# Main.net
KiCad netlist of a schematic drawn in Altium Designer
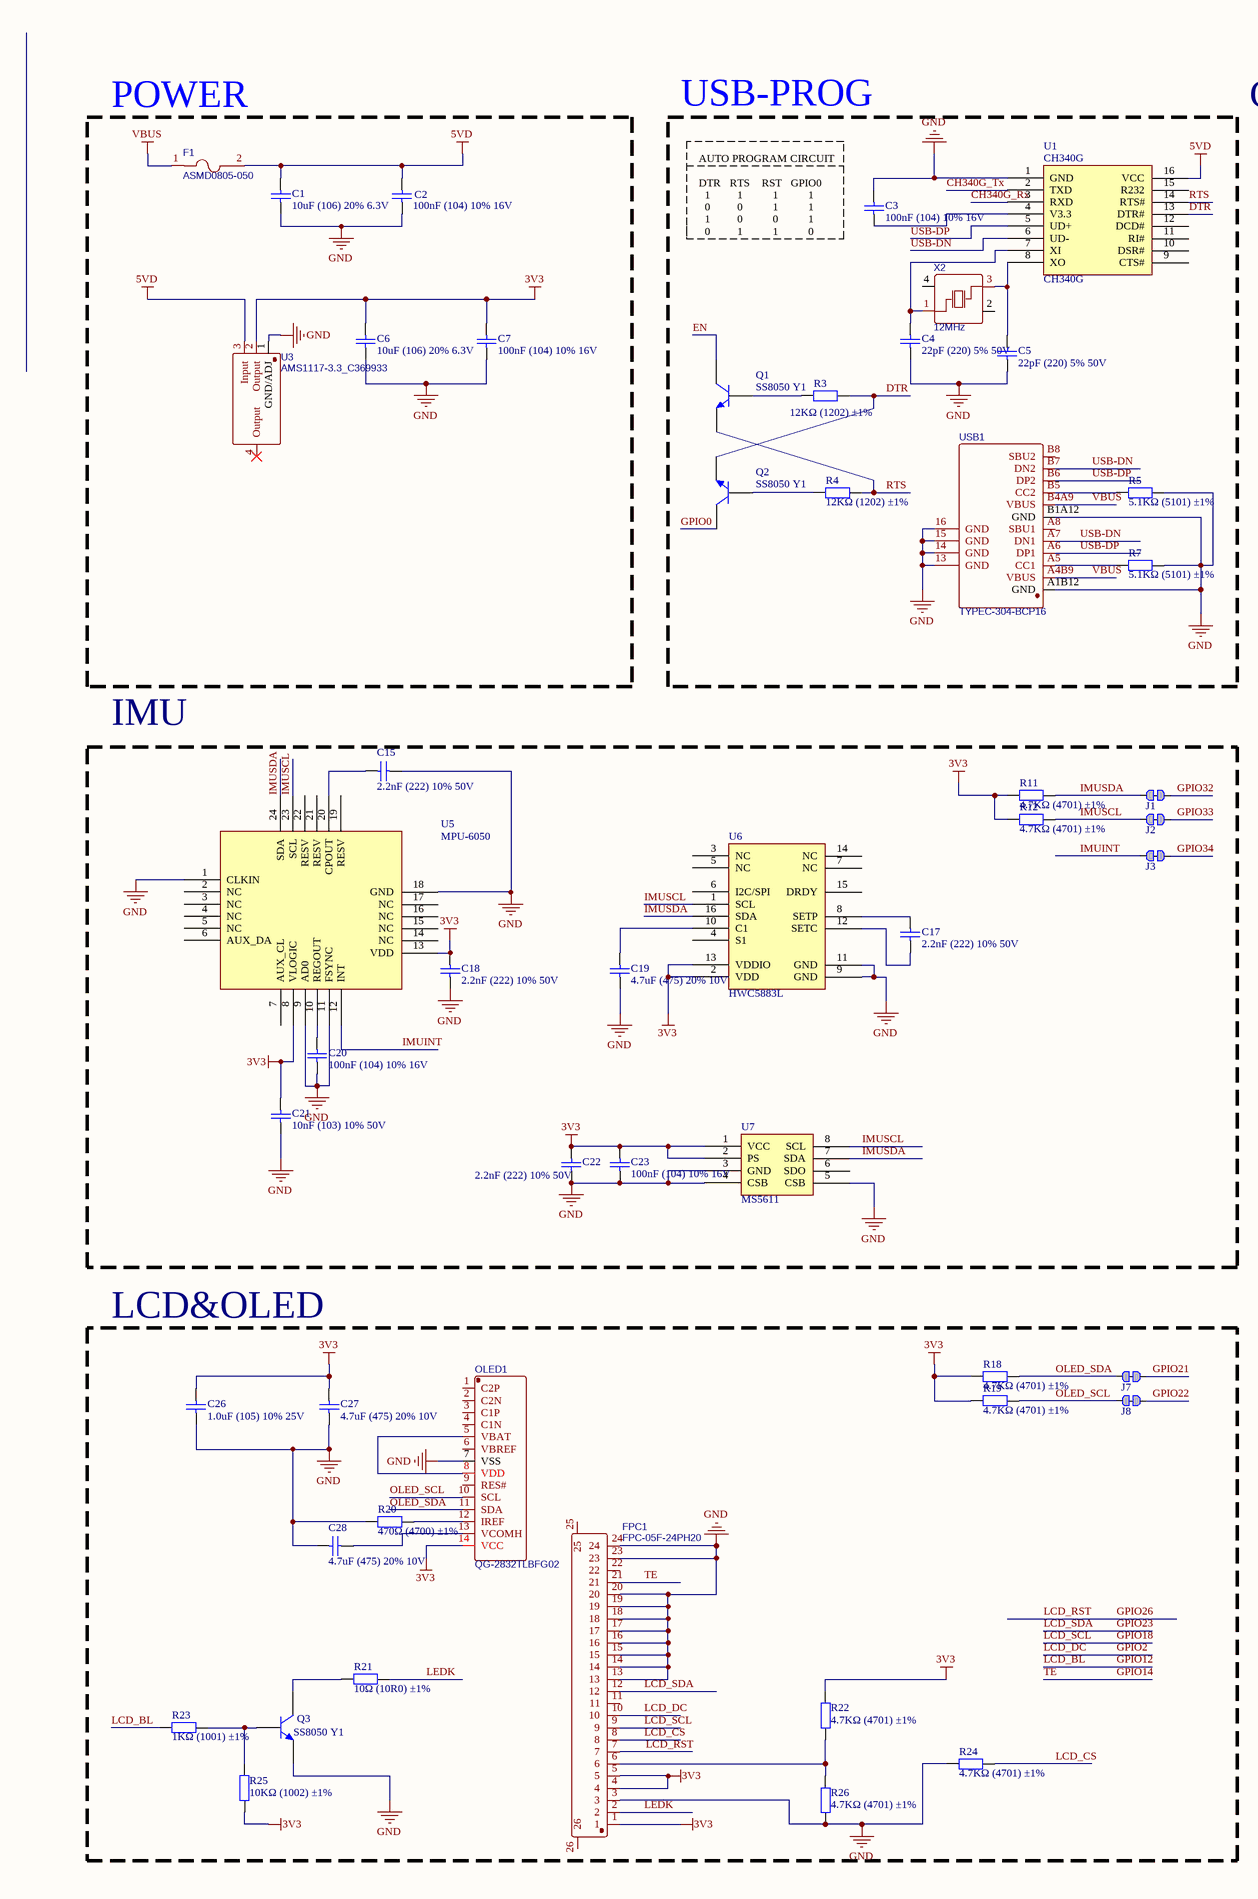
[diagram p0: Main.SchDoc, left]
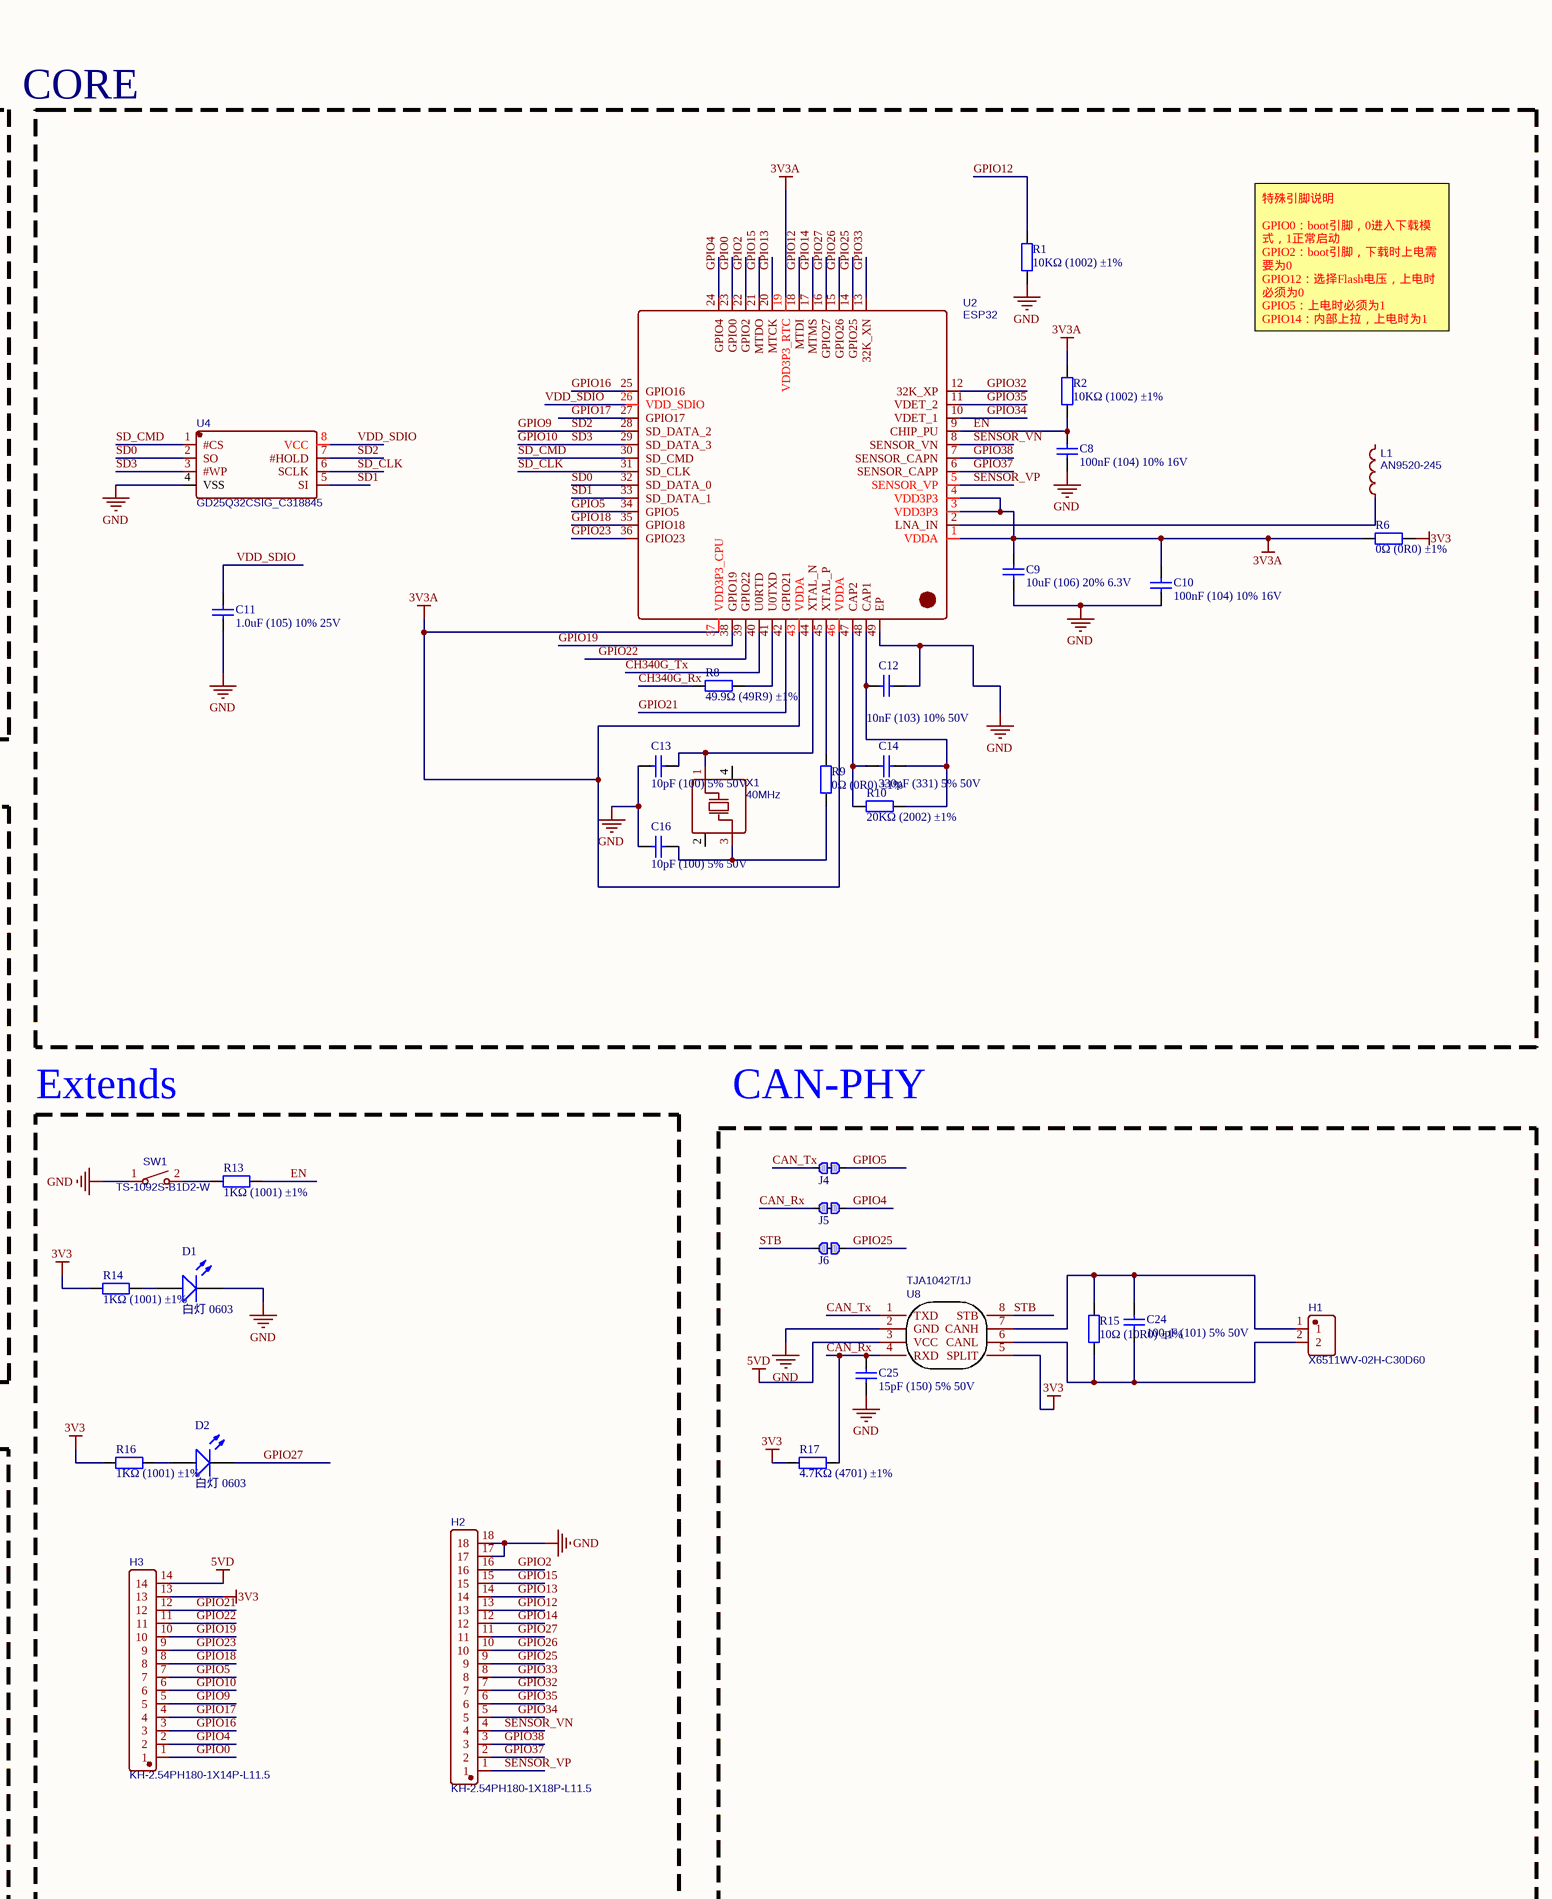
[diagram p1: Main.SchDoc, right]

(export (version "E")
  (design (tool "Eeschema 10.0.6"))
  (components
    (comp (ref "C1")
      (value "10uF (106) 20% 6.3V")
      (footprint "0402_C")
      (description "贴片电容")
      (libsource (lib "Cap") (part "0402 10uF (106) 20% 6.3V"))
    )
    (comp (ref "C2")
      (value "100nF (104) 10% 16V")
      (footprint "0402_C")
      (description "贴片电容")
      (libsource (lib "Cap") (part "0402 100nF (104) 10% 16V"))
    )
    (comp (ref "C3")
      (value "100nF (104) 10% 16V")
      (footprint "0402_C")
      (description "贴片电容")
      (libsource (lib "Cap") (part "0402 100nF (104) 10% 16V"))
    )
    (comp (ref "C4")
      (value "22pF (220) 5% 50V")
      (footprint "0402_C")
      (description "贴片电容")
      (libsource (lib "Cap") (part "0402 22pF (220) 5% 50V"))
    )
    (comp (ref "C5")
      (value "22pF (220) 5% 50V")
      (footprint "0402_C")
      (description "贴片电容")
      (libsource (lib "Cap") (part "0402 22pF (220) 5% 50V"))
    )
    (comp (ref "C6")
      (value "10uF (106) 20% 6.3V")
      (footprint "0402_C")
      (description "贴片电容")
      (libsource (lib "Cap") (part "0402 10uF (106) 20% 6.3V"))
    )
    (comp (ref "C7")
      (value "100nF (104) 10% 16V")
      (footprint "0402_C")
      (description "贴片电容")
      (libsource (lib "Cap") (part "0402 100nF (104) 10% 16V"))
    )
    (comp (ref "C8")
      (value "100nF (104) 10% 16V")
      (footprint "0402_C")
      (description "贴片电容")
      (libsource (lib "Cap") (part "0402 100nF (104) 10% 16V"))
    )
    (comp (ref "C9")
      (value "10uF (106) 20% 6.3V")
      (footprint "0402_C")
      (description "贴片电容")
      (libsource (lib "Cap") (part "0402 10uF (106) 20% 6.3V"))
    )
    (comp (ref "C10")
      (value "100nF (104) 10% 16V")
      (footprint "0402_C")
      (description "贴片电容")
      (libsource (lib "Cap") (part "0402 100nF (104) 10% 16V"))
    )
    (comp (ref "C11")
      (value "1.0uF (105) 10% 25V")
      (footprint "0402_C")
      (description "贴片电容")
      (libsource (lib "Cap") (part "0402 1.0uF (105) 10% 25V"))
    )
    (comp (ref "C12")
      (value "10nF (103) 10% 50V")
      (footprint "0402_C")
      (description "贴片电容")
      (libsource (lib "Cap") (part "0402 10nF (103) 10% 50V"))
    )
    (comp (ref "C13")
      (value "10pF (100) 5% 50V")
      (footprint "0402_C")
      (description "贴片电容")
      (libsource (lib "Cap") (part "0402 10pF (100) 5% 50V"))
    )
    (comp (ref "C14")
      (value "330pF (331) 5% 50V")
      (footprint "0402_C")
      (description "贴片电容")
      (libsource (lib "Cap") (part "0402 330pF (331) 5% 50V"))
    )
    (comp (ref "C15")
      (value "2.2nF (222) 10% 50V")
      (footprint "0402_C")
      (description "贴片电容")
      (libsource (lib "Cap") (part "0402 2.2nF (222) 10% 50V"))
    )
    (comp (ref "C16")
      (value "10pF (100) 5% 50V")
      (footprint "0402_C")
      (description "贴片电容")
      (libsource (lib "Cap") (part "0402 10pF (100) 5% 50V"))
    )
    (comp (ref "C17")
      (value "2.2nF (222) 10% 50V")
      (footprint "0402_C")
      (description "贴片电容")
      (libsource (lib "Cap") (part "0402 2.2nF (222) 10% 50V"))
    )
    (comp (ref "C18")
      (value "2.2nF (222) 10% 50V")
      (footprint "0402_C")
      (description "贴片电容")
      (libsource (lib "Cap") (part "0402 2.2nF (222) 10% 50V"))
    )
    (comp (ref "C19")
      (value "4.7uF (475) 20% 10V")
      (footprint "0402_C")
      (description "贴片电容")
      (libsource (lib "Cap") (part "0402 4.7uF (475) 20% 10V"))
    )
    (comp (ref "C20")
      (value "100nF (104) 10% 16V")
      (footprint "0402_C")
      (description "贴片电容")
      (libsource (lib "Cap") (part "0402 100nF (104) 10% 16V"))
    )
    (comp (ref "C21")
      (value "10nF (103) 10% 50V")
      (footprint "0402_C")
      (description "贴片电容")
      (libsource (lib "Cap") (part "0402 10nF (103) 10% 50V"))
    )
    (comp (ref "C22")
      (value "2.2nF (222) 10% 50V")
      (footprint "0402_C")
      (description "贴片电容")
      (libsource (lib "Cap") (part "0402 2.2nF (222) 10% 50V"))
    )
    (comp (ref "C23")
      (value "100nF (104) 10% 16V")
      (footprint "0402_C")
      (description "贴片电容")
      (libsource (lib "Cap") (part "0402 100nF (104) 10% 16V"))
    )
    (comp (ref "C24")
      (value "100pF (101) 5% 50V")
      (footprint "0402_C")
      (description "贴片电容")
      (libsource (lib "Cap") (part "0402 100pF (101) 5% 50V"))
    )
    (comp (ref "C25")
      (value "15pF (150) 5% 50V")
      (footprint "0402_C")
      (description "贴片电容")
      (libsource (lib "Cap") (part "0402 15pF (150) 5% 50V"))
    )
    (comp (ref "C26")
      (value "1.0uF (105) 10% 25V")
      (footprint "0402_C")
      (description "贴片电容")
      (libsource (lib "Cap") (part "0402 1.0uF (105) 10% 25V"))
    )
    (comp (ref "C27")
      (value "4.7uF (475) 20% 10V")
      (footprint "0402_C")
      (description "贴片电容")
      (libsource (lib "Cap") (part "0402 4.7uF (475) 20% 10V"))
    )
    (comp (ref "C28")
      (value "4.7uF (475) 20% 10V")
      (footprint "0402_C")
      (description "贴片电容")
      (libsource (lib "Cap") (part "0402 4.7uF (475) 20% 10V"))
    )
    (comp (ref "D1")
      (value "白灯 0603")
      (footprint "0603_LED_S1")
      (description "发光二极管")
      (libsource (lib "Miscellaneous Devices LC") (part "0603 白灯"))
    )
    (comp (ref "D2")
      (value "白灯 0603")
      (footprint "0603_LED_S1")
      (description "发光二极管")
      (libsource (lib "Miscellaneous Devices LC") (part "0603 白灯"))
    )
    (comp (ref "F1")
      (value "ASMD0805-050")
      (footprint "F0805")
      (fields (field (name "BOM_SUPPLIER PART") "C135329") (field (name "CONTRIBUTOR") "LCSC"))
      (libsource (lib "mypkg") (part "ASMD0805-050"))
    )
    (comp (ref "FPC1")
      (value "FPC-05F-24PH20")
      (footprint "FPC-SMD_24P-P0.50_FPC-05F-24PH20")
      (description "FPC24脚")
      (fields (field (name "BOM_SUPPLIER PART") "C2856805") (field (name "CONTRIBUTOR") "LCSC"))
      (libsource (lib "mysch") (part "FPC-05F-24PH20"))
    )
    (comp (ref "H1")
      (value "X6511WV-02H-C30D60")
      (footprint "HDR-TH_2P-P2.54-V-M")
      (fields (field (name "BOM_SUPPLIER PART") "C706874") (field (name "CONTRIBUTOR") "LCSC"))
      (libsource (lib "mysch") (part "HDR-2P"))
    )
    (comp (ref "H2")
      (value "KH-2.54PH180-1X18P-L11.5")
      (footprint "HDR-TH_18P-P2.54-V-M")
      (fields (field (name "BOM_SUPPLIER PART") "C2905492") (field (name "CONTRIBUTOR") "LCSC"))
      (libsource (lib "mysch") (part "HDR-18P"))
    )
    (comp (ref "H3")
      (value "KH-2.54PH180-1X14P-L11.5")
      (footprint "HDR-TH_14P-P2.54-V-M")
      (description "排针")
      (fields (field (name "BOM_SUPPLIER PART") "C2905490") (field (name "CONTRIBUTOR") "LCSC"))
      (libsource (lib "mysch") (part "HDR-14P"))
    )
    (comp (ref "J1")
      (value "跳线")
      (footprint "RES_0402")
      (description "Resistor")
      (fields (field (name "PUBLISHER") "Altium Limited"))
      (libsource (lib "mysch") (part "跳线"))
    )
    (comp (ref "J2")
      (value "跳线")
      (footprint "RES_0402")
      (description "Resistor")
      (fields (field (name "PUBLISHER") "Altium Limited"))
      (libsource (lib "mysch") (part "跳线"))
    )
    (comp (ref "J3")
      (value "跳线")
      (footprint "RES_0402")
      (description "Resistor")
      (fields (field (name "PUBLISHER") "Altium Limited"))
      (libsource (lib "mysch") (part "跳线"))
    )
    (comp (ref "J4")
      (value "跳线")
      (footprint "RES_0402")
      (description "Resistor")
      (fields (field (name "PUBLISHER") "Altium Limited"))
      (libsource (lib "mysch") (part "跳线"))
    )
    (comp (ref "J5")
      (value "跳线")
      (footprint "RES_0402")
      (description "Resistor")
      (fields (field (name "PUBLISHER") "Altium Limited"))
      (libsource (lib "mysch") (part "跳线"))
    )
    (comp (ref "J6")
      (value "跳线")
      (footprint "RES_0402")
      (description "Resistor")
      (fields (field (name "PUBLISHER") "Altium Limited"))
      (libsource (lib "mysch") (part "跳线"))
    )
    (comp (ref "J7")
      (value "跳线")
      (footprint "RES_0402")
      (description "Resistor")
      (fields (field (name "PUBLISHER") "Altium Limited"))
      (libsource (lib "mysch") (part "跳线"))
    )
    (comp (ref "J8")
      (value "跳线")
      (footprint "RES_0402")
      (description "Resistor")
      (fields (field (name "PUBLISHER") "Altium Limited"))
      (libsource (lib "mysch") (part "跳线"))
    )
    (comp (ref "L1")
      (value "AN9520-245")
      (footprint "ANT-SMD_L9.5-W2.1")
      (description "陶瓷wifi/bt天线")
      (fields (field (name "BOM_SUPPLIER PART") "C99665"))
      (libsource (lib "mypkg") (part "AN9520-245"))
    )
    (comp (ref "OLED1")
      (value "QG-2832TLBFG02")
      (footprint "OLED-SMD_QG-9616TSWCG02")
      (fields (field (name "BOM_SUPPLIER PART") "C91220") (field (name "CONTRIBUTOR") "LCSC"))
      (libsource (lib "mysch") (part "OLED"))
    )
    (comp (ref "Q1")
      (value "SS8050 Y1")
      (footprint "SOT-23(SOT-23-3)")
      (description "三极管")
      (libsource (lib "Miscellaneous Devices LC") (part "SOT-23 SS8050 Y1"))
    )
    (comp (ref "Q2")
      (value "SS8050 Y1")
      (footprint "SOT-23(SOT-23-3)")
      (description "三极管")
      (libsource (lib "Miscellaneous Devices LC") (part "SOT-23 SS8050 Y1"))
    )
    (comp (ref "Q3")
      (value "SS8050 Y1")
      (footprint "SOT-23(SOT-23-3)")
      (description "三极管")
      (libsource (lib "Miscellaneous Devices LC") (part "SOT-23 SS8050 Y1"))
    )
    (comp (ref "R1")
      (value "10KΩ (1002) ±1%")
      (footprint "0402_R")
      (description "贴片电阻")
      (libsource (lib "RES") (part "0402 10KΩ (1002) 1%"))
    )
    (comp (ref "R2")
      (value "10KΩ (1002) ±1%")
      (footprint "0402_R")
      (description "贴片电阻")
      (libsource (lib "RES") (part "0402 10KΩ (1002) 1%"))
    )
    (comp (ref "R3")
      (value "12KΩ (1202) ±1%")
      (footprint "0402_R")
      (description "贴片电阻")
      (libsource (lib "RES") (part "0402 12KΩ (1202) 1%"))
    )
    (comp (ref "R4")
      (value "12KΩ (1202) ±1%")
      (footprint "0402_R")
      (description "贴片电阻")
      (libsource (lib "RES") (part "0402 12KΩ (1202) 1%"))
    )
    (comp (ref "R5")
      (value "5.1KΩ (5101) ±1%")
      (footprint "0402_R")
      (description "贴片电阻")
      (libsource (lib "RES") (part "0402 5.1KΩ (5101) 1%"))
    )
    (comp (ref "R6")
      (value "0Ω (0R0) ±1%")
      (footprint "0402_R")
      (description "贴片电阻")
      (libsource (lib "RES") (part "0402 0Ω (0R0) 1%"))
    )
    (comp (ref "R7")
      (value "5.1KΩ (5101) ±1%")
      (footprint "0402_R")
      (description "贴片电阻")
      (libsource (lib "RES") (part "0402 5.1KΩ (5101) 1%"))
    )
    (comp (ref "R8")
      (value "49.9Ω (49R9) ±1%")
      (footprint "0402_R")
      (description "贴片电阻")
      (libsource (lib "RES") (part "0402 49.9Ω (49R9) 1%"))
    )
    (comp (ref "R9")
      (value "0Ω (0R0) ±1%")
      (footprint "0402_R")
      (description "贴片电阻")
      (libsource (lib "") (part "0402 0Ω (0R0) 1%_1"))
    )
    (comp (ref "R10")
      (value "20KΩ (2002) ±1%")
      (footprint "0402_R")
      (description "贴片电阻")
      (libsource (lib "RES") (part "0402 20KΩ (2002) 1%"))
    )
    (comp (ref "R11")
      (value "4.7KΩ (4701) ±1%")
      (footprint "0402_R")
      (description "贴片电阻")
      (libsource (lib "") (part "0402 4.7KΩ (4701) 1%_1"))
    )
    (comp (ref "R12")
      (value "4.7KΩ (4701) ±1%")
      (footprint "0402_R")
      (description "贴片电阻")
      (libsource (lib "") (part "0402 4.7KΩ (4701) 1%_1"))
    )
    (comp (ref "R13")
      (value "1KΩ (1001) ±1%")
      (footprint "0402_R")
      (description "贴片电阻")
      (libsource (lib "RES") (part "0402 1KΩ (1001) 1%"))
    )
    (comp (ref "R14")
      (value "1KΩ (1001) ±1%")
      (footprint "0402_R")
      (description "贴片电阻")
      (libsource (lib "RES") (part "0402 1KΩ (1001) 1%"))
    )
    (comp (ref "R15")
      (value "10Ω (10R0) ±1%")
      (footprint "0402_R")
      (description "贴片电阻")
      (libsource (lib "") (part "0402 10Ω (10R0) 1%_1"))
    )
    (comp (ref "R16")
      (value "1KΩ (1001) ±1%")
      (footprint "0402_R")
      (description "贴片电阻")
      (libsource (lib "RES") (part "0402 1KΩ (1001) 1%"))
    )
    (comp (ref "R17")
      (value "4.7KΩ (4701) ±1%")
      (footprint "0402_R")
      (description "贴片电阻")
      (libsource (lib "") (part "0402 4.7KΩ (4701) 1%_1"))
    )
    (comp (ref "R18")
      (value "4.7KΩ (4701) ±1%")
      (footprint "0402_R")
      (description "贴片电阻")
      (libsource (lib "") (part "0402 4.7KΩ (4701) 1%_1"))
    )
    (comp (ref "R19")
      (value "4.7KΩ (4701) ±1%")
      (footprint "0402_R")
      (description "贴片电阻")
      (libsource (lib "") (part "0402 4.7KΩ (4701) 1%_1"))
    )
    (comp (ref "R20")
      (value "470Ω (4700) ±1%")
      (footprint "0402_R")
      (description "贴片电阻")
      (libsource (lib "RES") (part "0402 470Ω (4700) 1%"))
    )
    (comp (ref "R21")
      (value "10Ω (10R0) ±1%")
      (footprint "0402_R")
      (description "贴片电阻")
      (libsource (lib "RES") (part "0402 10Ω (10R0) 1%"))
    )
    (comp (ref "R22")
      (value "4.7KΩ (4701) ±1%")
      (footprint "0402_R")
      (description "贴片电阻")
      (libsource (lib "RES") (part "0402 4.7KΩ (4701) 1%"))
    )
    (comp (ref "R23")
      (value "1KΩ (1001) ±1%")
      (footprint "0402_R")
      (description "贴片电阻")
      (libsource (lib "RES") (part "0402 1KΩ (1001) 1%"))
    )
    (comp (ref "R24")
      (value "4.7KΩ (4701) ±1%")
      (footprint "0402_R")
      (description "贴片电阻")
      (libsource (lib "") (part "0402 4.7KΩ (4701) 1%_1"))
    )
    (comp (ref "R25")
      (value "10KΩ (1002) ±1%")
      (footprint "0402_R")
      (description "贴片电阻")
      (libsource (lib "RES") (part "0402 10KΩ (1002) 1%"))
    )
    (comp (ref "R26")
      (value "4.7KΩ (4701) ±1%")
      (footprint "0402_R")
      (description "贴片电阻")
      (libsource (lib "RES") (part "0402 4.7KΩ (4701) 1%"))
    )
    (comp (ref "SW1")
      (value "TS-1092S-B1D2-W")
      (footprint "SW-SMD_L6.1-W3.6-LS7.9")
      (description "触控开关")
      (fields (field (name "BOM_SUPPLIER PART") "C782859") (field (name "CONTRIBUTOR") "LCSC"))
      (libsource (lib "mysch") (part "TS-1092S-B1D2-W"))
    )
    (comp (ref "U1")
      (value "CH340G")
      (footprint "SOIC-16_150mil")
      (description "USB")
      (libsource (lib "IC") (part "CH340G_[C14267]"))
    )
    (comp (ref "U2")
      (value "ESP32")
      (footprint "QFN-48-EP3.8")
      (fields (field (name "BOM_SUPPLIER PART") "C80134"))
      (libsource (lib "mypkg") (part "ESP32"))
    )
    (comp (ref "U3")
      (value "AMS1117-3.3_C369933")
      (footprint "SOT-223-3_L6.5-W3.4-P2.30-LS7.0-BR")
      (fields
        (field (name "BOM_SUPPLIER PART") "C369933")
        (field (name "BOM_MANUFACTURER PART") "AMS1117-3.3")
        (field (name "CONTRIBUTOR") "LCSC")
      )
      (libsource (lib "mysch") (part "AMS1117-3.3"))
    )
    (comp (ref "U4")
      (value "GD25Q32CSIG_C318845")
      (footprint "SOIC-8_L5.3-W5.3-P1.27-LS8.0-BL")
      (fields
        (field (name "BOM_SUPPLIER PART") "C318845")
        (field (name "BOM_MANUFACTURER PART") "GD25Q32CSIG")
        (field (name "CONTRIBUTOR") "LCSC")
      )
      (libsource (lib "mysch") (part "GD25Q32CSIG_C318845"))
    )
    (comp (ref "U5")
      (value "MPU-6050")
      (footprint "QFN-24_4x4x05P")
      (description "传感器")
      (libsource (lib "IC") (part "MPU-6050_[C24112]"))
    )
    (comp (ref "U6")
      (value "HWC5883L")
      (footprint "LPCC-16_L3.0-W3.0-P0.50-BL")
      (libsource (lib "mypkg") (part "HMC5883L"))
    )
    (comp (ref "U7") (value "MS5611") (footprint "MS5611") (libsource (lib "mysch") (part "MS5611")))
    (comp (ref "U8")
      (value "TJA1042T/1J")
      (footprint "SOIC-8_L5.0-W4.0-P1.27-LS6.0-BL")
      (description "CAN芯片")
      (fields (field (name "BOM_SUPPLIER PART") "C53670"))
      (libsource (lib "mysch") (part "TJA1042T/1J"))
    )
    (comp (ref "USB1")
      (value "TYPEC-304-BCP16")
      (footprint "USB-C-SMD_TYPEC-304-BCP16")
      (fields (field (name "BOM_SUPPLIER PART") "C720629") (field (name "CONTRIBUTOR") "LCSC"))
      (libsource (lib "mysch") (part "TYPEC-304-BCP16"))
    )
    (comp (ref "X1")
      (value "40MHz")
      (footprint "OSC-SMD_4P-L3.2-W2.5-BL")
      (description "有源晶振")
      (fields
        (field (name "BOM_SUPPLIER PART") "C337680")
        (field (name "BOM_MANUFACTURER PART") "3225-20MHZ-15PF-10PPM")
        (field (name "CONTRIBUTOR") "LCSC")
      )
      (libsource (lib "mysch") (part "40MHz"))
    )
    (comp (ref "X2")
      (value "12MHz")
      (footprint "OSC-SMD_4P-L3.2-W2.5-BL")
      (description "无源晶振")
      (fields
        (field (name "BOM_MANUFACTURER PART") "X322512MSB4SI")
        (field (name "BOM_SUPPLIER PART") "C9002")
      )
      (libsource (lib "mysch") (part "12MHz"))
    )
  )
  (nets
    (net (code "1") (name "/CAN_Rx") (class "Default")
      (node (ref "C25") (pin "2") (pinfunction "2_2") (pintype "passive"))
      (node (ref "J5") (pin "1") (pinfunction "1_1") (pintype "passive"))
      (node (ref "R17") (pin "2") (pinfunction "2_2") (pintype "passive"))
      (node (ref "U8") (pin "4") (pinfunction "RXD_4") (pintype "passive"))
    )
    (net (code "2") (name "/CAN_Tx") (class "Default")
      (node (ref "J4") (pin "1") (pinfunction "1_1") (pintype "passive"))
      (node (ref "U8") (pin "1") (pinfunction "TXD_1") (pintype "passive"))
    )
    (net (code "3") (name "/CH340G_Rx") (class "Default")
      (node (ref "R8") (pin "1") (pinfunction "1_1") (pintype "passive"))
      (node (ref "U1") (pin "3") (pinfunction "RXD_3") (pintype "passive"))
    )
    (net (code "4") (name "/CH340G_Tx") (class "Default")
      (node (ref "U1") (pin "2") (pinfunction "TXD_2") (pintype "passive"))
      (node (ref "U2") (pin "40") (pinfunction "U0RTD_40") (pintype "passive"))
    )
    (net (code "5") (name "/DTR") (class "Default")
      (node (ref "Q2") (pin "2") (pinfunction "E_2") (pintype "passive"))
      (node (ref "R3") (pin "2") (pinfunction "2_2") (pintype "passive"))
      (node (ref "U1") (pin "13") (pinfunction "DTR#_13") (pintype "passive"))
    )
    (net (code "6") (name "/EN") (class "Default")
      (node (ref "C8") (pin "2") (pinfunction "2_2") (pintype "passive"))
      (node (ref "Q1") (pin "3") (pinfunction "C_3") (pintype "passive"))
      (node (ref "R13") (pin "2") (pinfunction "2_2") (pintype "passive"))
      (node (ref "R2") (pin "1") (pinfunction "1_1") (pintype "passive"))
      (node (ref "U2") (pin "9") (pinfunction "CHIP_PU_9") (pintype "passive"))
    )
    (net (code "7") (name "/GPIO0") (class "Default")
      (node (ref "H3") (pin "1") (pinfunction "1_1") (pintype "passive"))
      (node (ref "Q2") (pin "3") (pinfunction "C_3") (pintype "passive"))
      (node (ref "U2") (pin "23") (pinfunction "GPIO0_23") (pintype "passive"))
    )
    (net (code "8") (name "/GPIO2") (class "Default")
      (node (ref "FPC1") (pin "10") (pinfunction "10_10") (pintype "passive"))
      (node (ref "H2") (pin "16") (pinfunction "16_16") (pintype "passive"))
      (node (ref "U2") (pin "22") (pinfunction "GPIO2_22") (pintype "passive"))
    )
    (net (code "9") (name "/GPIO4") (class "Default")
      (node (ref "H3") (pin "2") (pinfunction "2_2") (pintype "passive"))
      (node (ref "J5") (pin "2") (pinfunction "2_2") (pintype "passive"))
      (node (ref "U2") (pin "24") (pinfunction "GPIO4_24") (pintype "passive"))
    )
    (net (code "10") (name "/GPIO5") (class "Default")
      (node (ref "H3") (pin "7") (pinfunction "7_7") (pintype "passive"))
      (node (ref "J4") (pin "2") (pinfunction "2_2") (pintype "passive"))
      (node (ref "U2") (pin "34") (pinfunction "GPIO5_34") (pintype "passive"))
    )
    (net (code "11") (name "/GPIO9") (class "Default")
      (node (ref "H3") (pin "5") (pinfunction "5_5") (pintype "passive"))
      (node (ref "U2") (pin "28") (pinfunction "SD_DATA_2_28") (pintype "passive"))
      (node (ref "U4") (pin "7") (pinfunction "#HOLD_7") (pintype "passive"))
    )
    (net (code "12") (name "/GPIO10") (class "Default")
      (node (ref "H3") (pin "6") (pinfunction "6_6") (pintype "passive"))
      (node (ref "U2") (pin "29") (pinfunction "SD_DATA_3_29") (pintype "passive"))
      (node (ref "U4") (pin "3") (pinfunction "#WP_3") (pintype "passive"))
    )
    (net (code "13") (name "/GPIO12") (class "Default")
      (node (ref "H2") (pin "13") (pinfunction "13_13") (pintype "passive"))
      (node (ref "R1") (pin "2") (pinfunction "2_2") (pintype "passive"))
      (node (ref "R23") (pin "1") (pinfunction "1_1") (pintype "passive"))
      (node (ref "U2") (pin "18") (pinfunction "MTDI_18") (pintype "passive"))
    )
    (net (code "14") (name "/GPIO13") (class "Default")
      (node (ref "H2") (pin "14") (pinfunction "14_14") (pintype "passive"))
      (node (ref "U2") (pin "20") (pinfunction "MTCK_20") (pintype "passive"))
    )
    (net (code "15") (name "/GPIO14") (class "Default")
      (node (ref "FPC1") (pin "21") (pinfunction "21_21") (pintype "passive"))
      (node (ref "H2") (pin "12") (pinfunction "12_12") (pintype "passive"))
      (node (ref "U2") (pin "17") (pinfunction "MTMS_17") (pintype "passive"))
    )
    (net (code "16") (name "/GPIO15") (class "Default")
      (node (ref "H2") (pin "15") (pinfunction "15_15") (pintype "passive"))
      (node (ref "U2") (pin "21") (pinfunction "MTDO_21") (pintype "passive"))
    )
    (net (code "17") (name "/GPIO16") (class "Default")
      (node (ref "H3") (pin "3") (pinfunction "3_3") (pintype "passive"))
      (node (ref "U2") (pin "25") (pinfunction "GPIO16_25") (pintype "passive"))
    )
    (net (code "18") (name "/GPIO17") (class "Default")
      (node (ref "H3") (pin "4") (pinfunction "4_4") (pintype "passive"))
      (node (ref "U2") (pin "27") (pinfunction "GPIO17_27") (pintype "passive"))
    )
    (net (code "19") (name "/GPIO18") (class "Default")
      (node (ref "FPC1") (pin "9") (pinfunction "9_9") (pintype "passive"))
      (node (ref "H3") (pin "8") (pinfunction "8_8") (pintype "passive"))
      (node (ref "U2") (pin "35") (pinfunction "GPIO18_35") (pintype "passive"))
    )
    (net (code "20") (name "/GPIO19") (class "Default")
      (node (ref "H3") (pin "10") (pinfunction "10_10") (pintype "passive"))
      (node (ref "U2") (pin "38") (pinfunction "GPIO19_38") (pintype "passive"))
    )
    (net (code "21") (name "/GPIO21") (class "Default")
      (node (ref "H3") (pin "12") (pinfunction "12_12") (pintype "passive"))
      (node (ref "J7") (pin "2") (pinfunction "2_2") (pintype "passive"))
      (node (ref "U2") (pin "42") (pinfunction "GPIO21_42") (pintype "passive"))
    )
    (net (code "22") (name "/GPIO22") (class "Default")
      (node (ref "H3") (pin "11") (pinfunction "11_11") (pintype "passive"))
      (node (ref "J8") (pin "2") (pinfunction "2_2") (pintype "passive"))
      (node (ref "U2") (pin "39") (pinfunction "GPIO22_39") (pintype "passive"))
    )
    (net (code "23") (name "/GPIO23") (class "Default")
      (node (ref "FPC1") (pin "12") (pinfunction "12_12") (pintype "passive"))
      (node (ref "H3") (pin "9") (pinfunction "9_9") (pintype "passive"))
      (node (ref "U2") (pin "36") (pinfunction "GPIO23_36") (pintype "passive"))
    )
    (net (code "24") (name "/GPIO25") (class "Default")
      (node (ref "H2") (pin "9") (pinfunction "9_9") (pintype "passive"))
      (node (ref "J6") (pin "2") (pinfunction "2_2") (pintype "passive"))
      (node (ref "U2") (pin "14") (pinfunction "GPIO25_14") (pintype "passive"))
    )
    (net (code "25") (name "/GPIO26") (class "Default")
      (node (ref "FPC1") (pin "7") (pinfunction "7_7") (pintype "passive"))
      (node (ref "H2") (pin "10") (pinfunction "10_10") (pintype "passive"))
      (node (ref "U2") (pin "15") (pinfunction "GPIO26_15") (pintype "passive"))
    )
    (net (code "26") (name "/GPIO27") (class "Default")
      (node (ref "D2") (pin "K") (pinfunction "K_K") (pintype "passive"))
      (node (ref "H2") (pin "11") (pinfunction "11_11") (pintype "passive"))
      (node (ref "U2") (pin "16") (pinfunction "GPIO27_16") (pintype "passive"))
    )
    (net (code "27") (name "/GPIO32") (class "Default")
      (node (ref "H2") (pin "7") (pinfunction "7_7") (pintype "passive"))
      (node (ref "J1") (pin "2") (pinfunction "2_2") (pintype "passive"))
      (node (ref "U2") (pin "12") (pinfunction "32K_XP_12") (pintype "passive"))
    )
    (net (code "28") (name "/GPIO33") (class "Default")
      (node (ref "H2") (pin "8") (pinfunction "8_8") (pintype "passive"))
      (node (ref "J2") (pin "2") (pinfunction "2_2") (pintype "passive"))
      (node (ref "U2") (pin "13") (pinfunction "32K_XN_13") (pintype "passive"))
    )
    (net (code "29") (name "/GPIO34") (class "Default")
      (node (ref "H2") (pin "5") (pinfunction "5_5") (pintype "passive"))
      (node (ref "J3") (pin "2") (pinfunction "2_2") (pintype "passive"))
      (node (ref "U2") (pin "10") (pinfunction "VDET_1_10") (pintype "passive"))
    )
    (net (code "30") (name "/GPIO35") (class "Default")
      (node (ref "H2") (pin "6") (pinfunction "6_6") (pintype "passive"))
      (node (ref "U2") (pin "11") (pinfunction "VDET_2_11") (pintype "passive"))
    )
    (net (code "31") (name "/GPIO37") (class "Default")
      (node (ref "H2") (pin "2") (pinfunction "2_2") (pintype "passive"))
      (node (ref "U2") (pin "6") (pinfunction "SENSOR_CAPP_6") (pintype "passive"))
    )
    (net (code "32") (name "/GPIO38") (class "Default")
      (node (ref "H2") (pin "3") (pinfunction "3_3") (pintype "passive"))
      (node (ref "U2") (pin "7") (pinfunction "SENSOR_CAPN_7") (pintype "passive"))
    )
    (net (code "33") (name "/IMUINT") (class "Default")
      (node (ref "J3") (pin "1") (pinfunction "1_1") (pintype "passive"))
      (node (ref "U5") (pin "12") (pinfunction "INT_12") (pintype "passive"))
    )
    (net (code "34") (name "/IMUSCL") (class "Default")
      (node (ref "J2") (pin "1") (pinfunction "1_1") (pintype "passive"))
      (node (ref "R12") (pin "2") (pinfunction "2_2") (pintype "passive"))
      (node (ref "U5") (pin "23") (pinfunction "SCL_23") (pintype "passive"))
      (node (ref "U6") (pin "1") (pinfunction "SCL_1") (pintype "passive"))
      (node (ref "U7") (pin "8") (pinfunction "SCL_8") (pintype "passive"))
    )
    (net (code "35") (name "/IMUSDA") (class "Default")
      (node (ref "J1") (pin "1") (pinfunction "1_1") (pintype "passive"))
      (node (ref "R11") (pin "2") (pinfunction "2_2") (pintype "passive"))
      (node (ref "U5") (pin "24") (pinfunction "SDA_24") (pintype "passive"))
      (node (ref "U6") (pin "16") (pinfunction "SDA_16") (pintype "passive"))
      (node (ref "U7") (pin "7") (pinfunction "SDA_7") (pintype "passive"))
    )
    (net (code "36") (name "/LCD_CS") (class "Default")
      (node (ref "FPC1") (pin "8") (pinfunction "8_8") (pintype "passive"))
      (node (ref "R24") (pin "2") (pinfunction "2_2") (pintype "passive"))
    )
    (net (code "37") (name "/LEDK") (class "Default")
      (node (ref "FPC1") (pin "2") (pinfunction "2_2") (pintype "passive"))
      (node (ref "R21") (pin "2") (pinfunction "2_2") (pintype "passive"))
    )
    (net (code "38") (name "/OLED_SCL") (class "Default")
      (node (ref "J8") (pin "1") (pinfunction "1_1") (pintype "passive"))
      (node (ref "OLED1") (pin "10") (pinfunction "SCL_10") (pintype "passive"))
      (node (ref "R19") (pin "2") (pinfunction "2_2") (pintype "passive"))
    )
    (net (code "39") (name "/OLED_SDA") (class "Default")
      (node (ref "J7") (pin "1") (pinfunction "1_1") (pintype "passive"))
      (node (ref "OLED1") (pin "11") (pinfunction "SDA_11") (pintype "passive"))
      (node (ref "R18") (pin "2") (pinfunction "2_2") (pintype "passive"))
    )
    (net (code "40") (name "/RTS") (class "Default")
      (node (ref "Q1") (pin "2") (pinfunction "E_2") (pintype "passive"))
      (node (ref "R4") (pin "2") (pinfunction "2_2") (pintype "passive"))
      (node (ref "U1") (pin "14") (pinfunction "RTS#_14") (pintype "passive"))
    )
    (net (code "41") (name "/SD0") (class "Default")
      (node (ref "U2") (pin "32") (pinfunction "SD_DATA_0_32") (pintype "passive"))
      (node (ref "U4") (pin "2") (pinfunction "SO_2") (pintype "passive"))
    )
    (net (code "42") (name "/SD1") (class "Default")
      (node (ref "U2") (pin "33") (pinfunction "SD_DATA_1_33") (pintype "passive"))
      (node (ref "U4") (pin "5") (pinfunction "SI_5") (pintype "passive"))
    )
    (net (code "43") (name "/SD_CLK") (class "Default")
      (node (ref "U2") (pin "31") (pinfunction "SD_CLK_31") (pintype "passive"))
      (node (ref "U4") (pin "6") (pinfunction "SCLK_6") (pintype "passive"))
    )
    (net (code "44") (name "/SD_CMD") (class "Default")
      (node (ref "U2") (pin "30") (pinfunction "SD_CMD_30") (pintype "passive"))
      (node (ref "U4") (pin "1") (pinfunction "#CS_1") (pintype "passive"))
    )
    (net (code "45") (name "/SENSOR_VN") (class "Default")
      (node (ref "H2") (pin "4") (pinfunction "4_4") (pintype "passive"))
      (node (ref "U2") (pin "8") (pinfunction "SENSOR_VN_8") (pintype "passive"))
    )
    (net (code "46") (name "/SENSOR_VP") (class "Default")
      (node (ref "H2") (pin "1") (pinfunction "1_1") (pintype "passive"))
      (node (ref "U2") (pin "5") (pinfunction "SENSOR_VP_5") (pintype "passive"))
    )
    (net (code "47") (name "/STB") (class "Default")
      (node (ref "J6") (pin "1") (pinfunction "1_1") (pintype "passive"))
      (node (ref "U8") (pin "8") (pinfunction "STB_8") (pintype "passive"))
    )
    (net (code "48") (name "/USB-DN") (class "Default")
      (node (ref "U1") (pin "6") (pinfunction "UD-_6") (pintype "passive"))
      (node (ref "USB1") (pin "A7") (pinfunction "DN1_A7") (pintype "passive"))
      (node (ref "USB1") (pin "B7") (pinfunction "DN2_B7") (pintype "passive"))
    )
    (net (code "49") (name "/USB-DP") (class "Default")
      (node (ref "U1") (pin "5") (pinfunction "UD+_5") (pintype "passive"))
      (node (ref "USB1") (pin "A6") (pinfunction "DP1_A6") (pintype "passive"))
      (node (ref "USB1") (pin "B6") (pinfunction "DP2_B6") (pintype "passive"))
    )
    (net (code "50") (name "/VDD_SDIO") (class "Default")
      (node (ref "C11") (pin "2") (pinfunction "2_2") (pintype "passive"))
      (node (ref "U2") (pin "26") (pinfunction "VDD_SDIO_26") (pintype "passive"))
      (node (ref "U4") (pin "8") (pinfunction "VCC_8") (pintype "passive"))
    )
    (net (code "51") (name "3V3") (class "Default")
      (node (ref "C18") (pin "2") (pinfunction "2_2") (pintype "passive"))
      (node (ref "C21") (pin "2") (pinfunction "2_2") (pintype "passive"))
      (node (ref "C22") (pin "2") (pinfunction "2_2") (pintype "passive"))
      (node (ref "C23") (pin "2") (pinfunction "2_2") (pintype "passive"))
      (node (ref "C26") (pin "2") (pinfunction "2_2") (pintype "passive"))
      (node (ref "C27") (pin "2") (pinfunction "2_2") (pintype "passive"))
      (node (ref "C6") (pin "2") (pinfunction "2_2") (pintype "passive"))
      (node (ref "C7") (pin "2") (pinfunction "2_2") (pintype "passive"))
      (node (ref "FPC1") (pin "1") (pinfunction "1_1") (pintype "passive"))
      (node (ref "FPC1") (pin "4") (pinfunction "4_4") (pintype "passive"))
      (node (ref "FPC1") (pin "5") (pinfunction "5_5") (pintype "passive"))
      (node (ref "H3") (pin "13") (pinfunction "13_13") (pintype "passive"))
      (node (ref "OLED1") (pin "14") (pinfunction "VCC_14") (pintype "passive"))
      (node (ref "R11") (pin "1") (pinfunction "1_1") (pintype "passive"))
      (node (ref "R12") (pin "1") (pinfunction "1_1") (pintype "passive"))
      (node (ref "R14") (pin "1") (pinfunction "1_1") (pintype "passive"))
      (node (ref "R16") (pin "1") (pinfunction "1_1") (pintype "passive"))
      (node (ref "R17") (pin "1") (pinfunction "1_1") (pintype "passive"))
      (node (ref "R18") (pin "1") (pinfunction "1_1") (pintype "passive"))
      (node (ref "R19") (pin "1") (pinfunction "1_1") (pintype "passive"))
      (node (ref "R22") (pin "2") (pinfunction "2_2") (pintype "passive"))
      (node (ref "R25") (pin "1") (pinfunction "1_1") (pintype "passive"))
      (node (ref "R6") (pin "2") (pinfunction "2_2") (pintype "passive"))
      (node (ref "U3") (pin "2") (pinfunction "Output_2") (pintype "passive"))
      (node (ref "U5") (pin "13") (pinfunction "VDD_13") (pintype "passive"))
      (node (ref "U5") (pin "8") (pinfunction "VLOGIC_8") (pintype "passive"))
      (node (ref "U6") (pin "13") (pinfunction "VDDIO_13") (pintype "passive"))
      (node (ref "U6") (pin "2") (pinfunction "VDD_2") (pintype "passive"))
      (node (ref "U7") (pin "1") (pinfunction "VCC_1") (pintype "passive"))
      (node (ref "U7") (pin "2") (pinfunction "PS_2") (pintype "passive"))
      (node (ref "U8") (pin "5") (pinfunction "SPLIT_5") (pintype "passive"))
    )
    (net (code "52") (name "3V3A") (class "Default")
      (node (ref "C10") (pin "2") (pinfunction "2_2") (pintype "passive"))
      (node (ref "C9") (pin "2") (pinfunction "2_2") (pintype "passive"))
      (node (ref "R2") (pin "2") (pinfunction "2_2") (pintype "passive"))
      (node (ref "R6") (pin "1") (pinfunction "1_1") (pintype "passive"))
      (node (ref "U2") (pin "1") (pinfunction "VDDA_1") (pintype "passive"))
      (node (ref "U2") (pin "19") (pinfunction "VDD3P3_RTC_19") (pintype "passive"))
      (node (ref "U2") (pin "3") (pinfunction "VDD3P3_3") (pintype "passive"))
      (node (ref "U2") (pin "37") (pinfunction "VDD3P3_CPU_37") (pintype "passive"))
      (node (ref "U2") (pin "4") (pinfunction "VDD3P3_4") (pintype "passive"))
      (node (ref "U2") (pin "43") (pinfunction "VDDA_43") (pintype "passive"))
      (node (ref "U2") (pin "46") (pinfunction "VDDA_46") (pintype "passive"))
    )
    (net (code "53") (name "5VD") (class "Default")
      (node (ref "C1") (pin "2") (pinfunction "2_2") (pintype "passive"))
      (node (ref "C2") (pin "2") (pinfunction "2_2") (pintype "passive"))
      (node (ref "F1") (pin "2") (pinfunction "2_2") (pintype "passive"))
      (node (ref "H3") (pin "14") (pinfunction "14_14") (pintype "passive"))
      (node (ref "U1") (pin "16") (pinfunction "VCC_16") (pintype "passive"))
      (node (ref "U3") (pin "3") (pinfunction "Input_3") (pintype "passive"))
      (node (ref "U8") (pin "3") (pinfunction "VCC_3") (pintype "passive"))
    )
    (net (code "54") (name "GND") (class "Default")
      (node (ref "C1") (pin "1") (pinfunction "1_1") (pintype "passive"))
      (node (ref "C10") (pin "1") (pinfunction "1_1") (pintype "passive"))
      (node (ref "C11") (pin "1") (pinfunction "1_1") (pintype "passive"))
      (node (ref "C12") (pin "2") (pinfunction "2_2") (pintype "passive"))
      (node (ref "C13") (pin "1") (pinfunction "1_1") (pintype "passive"))
      (node (ref "C15") (pin "2") (pinfunction "2_2") (pintype "passive"))
      (node (ref "C16") (pin "1") (pinfunction "1_1") (pintype "passive"))
      (node (ref "C18") (pin "1") (pinfunction "1_1") (pintype "passive"))
      (node (ref "C19") (pin "1") (pinfunction "1_1") (pintype "passive"))
      (node (ref "C2") (pin "1") (pinfunction "1_1") (pintype "passive"))
      (node (ref "C20") (pin "1") (pinfunction "1_1") (pintype "passive"))
      (node (ref "C21") (pin "1") (pinfunction "1_1") (pintype "passive"))
      (node (ref "C22") (pin "1") (pinfunction "1_1") (pintype "passive"))
      (node (ref "C23") (pin "1") (pinfunction "1_1") (pintype "passive"))
      (node (ref "C25") (pin "1") (pinfunction "1_1") (pintype "passive"))
      (node (ref "C26") (pin "1") (pinfunction "1_1") (pintype "passive"))
      (node (ref "C27") (pin "1") (pinfunction "1_1") (pintype "passive"))
      (node (ref "C28") (pin "1") (pinfunction "1_1") (pintype "passive"))
      (node (ref "C3") (pin "2") (pinfunction "2_2") (pintype "passive"))
      (node (ref "C4") (pin "1") (pinfunction "1_1") (pintype "passive"))
      (node (ref "C5") (pin "1") (pinfunction "1_1") (pintype "passive"))
      (node (ref "C6") (pin "1") (pinfunction "1_1") (pintype "passive"))
      (node (ref "C7") (pin "1") (pinfunction "1_1") (pintype "passive"))
      (node (ref "C8") (pin "1") (pinfunction "1_1") (pintype "passive"))
      (node (ref "C9") (pin "1") (pinfunction "1_1") (pintype "passive"))
      (node (ref "D1") (pin "K") (pinfunction "K_K") (pintype "passive"))
      (node (ref "FPC1") (pin "13") (pinfunction "13_13") (pintype "passive"))
      (node (ref "FPC1") (pin "14") (pinfunction "14_14") (pintype "passive"))
      (node (ref "FPC1") (pin "15") (pinfunction "15_15") (pintype "passive"))
      (node (ref "FPC1") (pin "16") (pinfunction "16_16") (pintype "passive"))
      (node (ref "FPC1") (pin "17") (pinfunction "17_17") (pintype "passive"))
      (node (ref "FPC1") (pin "18") (pinfunction "18_18") (pintype "passive"))
      (node (ref "FPC1") (pin "19") (pinfunction "19_19") (pintype "passive"))
      (node (ref "FPC1") (pin "20") (pinfunction "20_20") (pintype "passive"))
      (node (ref "FPC1") (pin "23") (pinfunction "23_23") (pintype "passive"))
      (node (ref "FPC1") (pin "24") (pinfunction "24_24") (pintype "passive"))
      (node (ref "FPC1") (pin "3") (pinfunction "3_3") (pintype "passive"))
      (node (ref "H2") (pin "17") (pinfunction "17_17") (pintype "passive"))
      (node (ref "H2") (pin "18") (pinfunction "18_18") (pintype "passive"))
      (node (ref "OLED1") (pin "7") (pinfunction "VSS_7") (pintype "passive"))
      (node (ref "Q3") (pin "2") (pinfunction "E_2") (pintype "passive"))
      (node (ref "R1") (pin "1") (pinfunction "1_1") (pintype "passive"))
      (node (ref "R20") (pin "1") (pinfunction "1_1") (pintype "passive"))
      (node (ref "R24") (pin "1") (pinfunction "1_1") (pintype "passive"))
      (node (ref "R26") (pin "1") (pinfunction "1_1") (pintype "passive"))
      (node (ref "R5") (pin "2") (pinfunction "2_2") (pintype "passive"))
      (node (ref "R7") (pin "2") (pinfunction "2_2") (pintype "passive"))
      (node (ref "SW1") (pin "1") (pinfunction "1_1") (pintype "passive"))
      (node (ref "U1") (pin "1") (pinfunction "GND_1") (pintype "passive"))
      (node (ref "U2") (pin "49") (pinfunction "EP_49") (pintype "passive"))
      (node (ref "U3") (pin "1") (pinfunction "GND/ADJ_1") (pintype "passive"))
      (node (ref "U4") (pin "4") (pinfunction "VSS_4") (pintype "passive"))
      (node (ref "U5") (pin "1") (pinfunction "CLKIN_1") (pintype "passive"))
      (node (ref "U5") (pin "11") (pinfunction "FSYNC_11") (pintype "passive"))
      (node (ref "U5") (pin "18") (pinfunction "GND_18") (pintype "passive"))
      (node (ref "U5") (pin "9") (pinfunction "AD0_9") (pintype "passive"))
      (node (ref "U6") (pin "11") (pinfunction "GND_11") (pintype "passive"))
      (node (ref "U6") (pin "9") (pinfunction "GND_9") (pintype "passive"))
      (node (ref "U7") (pin "3") (pinfunction "GND_3") (pintype "passive"))
      (node (ref "U7") (pin "4") (pinfunction "CSB_4") (pintype "passive"))
      (node (ref "U7") (pin "5") (pinfunction "CSB_5") (pintype "passive"))
      (node (ref "U8") (pin "2") (pinfunction "GND_2") (pintype "passive"))
      (node (ref "USB1") (pin "13") (pinfunction "GND_13") (pintype "passive"))
      (node (ref "USB1") (pin "14") (pinfunction "GND_14") (pintype "passive"))
      (node (ref "USB1") (pin "15") (pinfunction "GND_15") (pintype "passive"))
      (node (ref "USB1") (pin "16") (pinfunction "GND_16") (pintype "passive"))
      (node (ref "USB1") (pin "A1B12") (pinfunction "GND_A1B12") (pintype "passive"))
      (node (ref "USB1") (pin "B1A12") (pinfunction "GND_B1A12") (pintype "passive"))
    )
    (net (code "55") (name "Net-(D1-PadA)") (class "Default")
      (node (ref "D1") (pin "A") (pinfunction "A_A") (pintype "passive"))
      (node (ref "R14") (pin "2") (pinfunction "2_2") (pintype "passive"))
    )
    (net (code "56") (name "Net-(D2-PadA)") (class "Default")
      (node (ref "D2") (pin "A") (pinfunction "A_A") (pintype "passive"))
      (node (ref "R16") (pin "2") (pinfunction "2_2") (pintype "passive"))
    )
    (net (code "57") (name "Net-(FPC1-Pad6)") (class "Default")
      (node (ref "FPC1") (pin "6") (pinfunction "6_6") (pintype "passive"))
      (node (ref "R22") (pin "1") (pinfunction "1_1") (pintype "passive"))
      (node (ref "R26") (pin "2") (pinfunction "2_2") (pintype "passive"))
    )
    (net (code "58") (name "Net-(OLED1-IREF)") (class "Default")
      (node (ref "OLED1") (pin "12") (pinfunction "IREF_12") (pintype "passive"))
      (node (ref "R20") (pin "2") (pinfunction "2_2") (pintype "passive"))
    )
    (net (code "59") (name "Net-(OLED1-VBAT)") (class "Default")
      (node (ref "OLED1") (pin "5") (pinfunction "VBAT_5") (pintype "passive"))
      (node (ref "OLED1") (pin "8") (pinfunction "VDD_8") (pintype "passive"))
    )
    (net (code "60") (name "Net-(OLED1-VCOMH)") (class "Default")
      (node (ref "C28") (pin "2") (pinfunction "2_2") (pintype "passive"))
      (node (ref "OLED1") (pin "13") (pinfunction "VCOMH_13") (pintype "passive"))
    )
    (net (code "61") (name "Net-(Q1-B)") (class "Default")
      (node (ref "Q1") (pin "1") (pinfunction "B_1") (pintype "passive"))
      (node (ref "R3") (pin "1") (pinfunction "1_1") (pintype "passive"))
    )
    (net (code "62") (name "Net-(Q2-B)") (class "Default")
      (node (ref "Q2") (pin "1") (pinfunction "B_1") (pintype "passive"))
      (node (ref "R4") (pin "1") (pinfunction "1_1") (pintype "passive"))
    )
    (net (code "63") (name "Net-(Q3-B)") (class "Default")
      (node (ref "Q3") (pin "1") (pinfunction "B_1") (pintype "passive"))
      (node (ref "R23") (pin "2") (pinfunction "2_2") (pintype "passive"))
      (node (ref "R25") (pin "2") (pinfunction "2_2") (pintype "passive"))
    )
    (net (code "64") (name "Net-(Q3-C)") (class "Default")
      (node (ref "Q3") (pin "3") (pinfunction "C_3") (pintype "passive"))
      (node (ref "R21") (pin "1") (pinfunction "1_1") (pintype "passive"))
    )
    (net (code "65") (name "Net-(R13-Pad1)") (class "Default")
      (node (ref "R13") (pin "1") (pinfunction "1_1") (pintype "passive"))
      (node (ref "SW1") (pin "2") (pinfunction "2_2") (pintype "passive"))
    )
    (net (code "66") (name "Net-(U1-V3.3)") (class "Default")
      (node (ref "C3") (pin "1") (pinfunction "1_1") (pintype "passive"))
      (node (ref "U1") (pin "4") (pinfunction "V3.3_4") (pintype "passive"))
    )
    (net (code "67") (name "Net-(U1-XI)") (class "Default")
      (node (ref "C4") (pin "2") (pinfunction "2_2") (pintype "passive"))
      (node (ref "U1") (pin "7") (pinfunction "XI_7") (pintype "passive"))
      (node (ref "X2") (pin "1") (pinfunction "OSC1_1") (pintype "passive"))
    )
    (net (code "68") (name "Net-(U1-XO)") (class "Default")
      (node (ref "C5") (pin "2") (pinfunction "2_2") (pintype "passive"))
      (node (ref "U1") (pin "8") (pinfunction "XO_8") (pintype "passive"))
      (node (ref "X2") (pin "3") (pinfunction "OSC2_3") (pintype "passive"))
    )
    (net (code "69") (name "Net-(U2-CAP1)") (class "Default")
      (node (ref "C12") (pin "1") (pinfunction "1_1") (pintype "passive"))
      (node (ref "C14") (pin "1") (pinfunction "1_1") (pintype "passive"))
      (node (ref "R10") (pin "2") (pinfunction "2_2") (pintype "passive"))
      (node (ref "U2") (pin "48") (pinfunction "CAP1_48") (pintype "passive"))
    )
    (net (code "70") (name "Net-(U2-CAP2)") (class "Default")
      (node (ref "C14") (pin "2") (pinfunction "2_2") (pintype "passive"))
      (node (ref "R10") (pin "1") (pinfunction "1_1") (pintype "passive"))
      (node (ref "U2") (pin "47") (pinfunction "CAP2_47") (pintype "passive"))
    )
    (net (code "71") (name "Net-(U2-LNA_IN)") (class "Default")
      (node (ref "L1") (pin "1") (pinfunction "1_1") (pintype "passive"))
      (node (ref "U2") (pin "2") (pinfunction "LNA_IN_2") (pintype "passive"))
    )
    (net (code "72") (name "Net-(U2-U0TXD)") (class "Default")
      (node (ref "R8") (pin "2") (pinfunction "2_2") (pintype "passive"))
      (node (ref "U2") (pin "41") (pinfunction "U0TXD_41") (pintype "passive"))
    )
    (net (code "73") (name "Net-(U2-XTAL_N)") (class "Default")
      (node (ref "C13") (pin "2") (pinfunction "2_2") (pintype "passive"))
      (node (ref "U2") (pin "44") (pinfunction "XTAL_N_44") (pintype "passive"))
      (node (ref "X1") (pin "1") (pinfunction "OSC1_1") (pintype "passive"))
    )
    (net (code "74") (name "Net-(U2-XTAL_P)") (class "Default")
      (node (ref "R9") (pin "2") (pinfunction "2_2") (pintype "passive"))
      (node (ref "U2") (pin "45") (pinfunction "XTAL_P_45") (pintype "passive"))
    )
    (net (code "75") (name "Net-(U5-CPOUT)") (class "Default")
      (node (ref "C15") (pin "1") (pinfunction "1_1") (pintype "passive"))
      (node (ref "U5") (pin "20") (pinfunction "CPOUT_20") (pintype "passive"))
    )
    (net (code "76") (name "Net-(U5-REGOUT)") (class "Default")
      (node (ref "C20") (pin "2") (pinfunction "2_2") (pintype "passive"))
      (node (ref "U5") (pin "10") (pinfunction "REGOUT_10") (pintype "passive"))
    )
    (net (code "77") (name "Net-(U6-C1)") (class "Default")
      (node (ref "C19") (pin "2") (pinfunction "2_2") (pintype "passive"))
      (node (ref "U6") (pin "10") (pinfunction "C1_10") (pintype "passive"))
    )
    (net (code "78") (name "Net-(U6-SETC)") (class "Default")
      (node (ref "C17") (pin "1") (pinfunction "1_1") (pintype "passive"))
      (node (ref "U6") (pin "12") (pinfunction "SETC_12") (pintype "passive"))
    )
    (net (code "79") (name "Net-(U6-SETP)") (class "Default")
      (node (ref "C17") (pin "2") (pinfunction "2_2") (pintype "passive"))
      (node (ref "U6") (pin "8") (pinfunction "SETP_8") (pintype "passive"))
    )
    (net (code "80") (name "Net-(U8-CANH)") (class "Default")
      (node (ref "C24") (pin "2") (pinfunction "2_2") (pintype "passive"))
      (node (ref "H1") (pin "1") (pinfunction "1_1") (pintype "passive"))
      (node (ref "R15") (pin "2") (pinfunction "2_2") (pintype "passive"))
      (node (ref "U8") (pin "7") (pinfunction "CANH_7") (pintype "passive"))
    )
    (net (code "81") (name "Net-(U8-CANL)") (class "Default")
      (node (ref "C24") (pin "1") (pinfunction "1_1") (pintype "passive"))
      (node (ref "H1") (pin "2") (pinfunction "2_2") (pintype "passive"))
      (node (ref "R15") (pin "1") (pinfunction "1_1") (pintype "passive"))
      (node (ref "U8") (pin "6") (pinfunction "CANL_6") (pintype "passive"))
    )
    (net (code "82") (name "Net-(USB1-CC1)") (class "Default")
      (node (ref "R7") (pin "1") (pinfunction "1_1") (pintype "passive"))
      (node (ref "USB1") (pin "A5") (pinfunction "CC1_A5") (pintype "passive"))
    )
    (net (code "83") (name "Net-(USB1-CC2)") (class "Default")
      (node (ref "R5") (pin "1") (pinfunction "1_1") (pintype "passive"))
      (node (ref "USB1") (pin "B5") (pinfunction "CC2_B5") (pintype "passive"))
    )
    (net (code "84") (name "Net-(X1-OSC2)") (class "Default")
      (node (ref "C16") (pin "2") (pinfunction "2_2") (pintype "passive"))
      (node (ref "R9") (pin "1") (pinfunction "1_1") (pintype "passive"))
      (node (ref "X1") (pin "3") (pinfunction "OSC2_3") (pintype "passive"))
    )
    (net (code "85") (name "VBUS") (class "Default")
      (node (ref "F1") (pin "1") (pinfunction "1_1") (pintype "passive"))
      (node (ref "USB1") (pin "A4B9") (pinfunction "VBUS_A4B9") (pintype "passive"))
      (node (ref "USB1") (pin "B4A9") (pinfunction "VBUS_B4A9") (pintype "passive"))
    )
    (net (code "86") (name "unconnected-(FPC1-Pad11)") (class "Default")
      (node (ref "FPC1") (pin "11") (pinfunction "11_11") (pintype "passive"))
    )
    (net (code "87") (name "unconnected-(FPC1-Pad22)") (class "Default")
      (node (ref "FPC1") (pin "22") (pinfunction "22_22") (pintype "passive"))
    )
    (net (code "88") (name "unconnected-(FPC1-Pad25)") (class "Default")
      (node (ref "FPC1") (pin "25") (pinfunction "25_25") (pintype "passive"))
    )
    (net (code "89") (name "unconnected-(FPC1-Pad26)") (class "Default")
      (node (ref "FPC1") (pin "26") (pinfunction "26_26") (pintype "passive"))
    )
    (net (code "90") (name "unconnected-(L1-Pad2)") (class "Default")
      (node (ref "L1") (pin "2") (pinfunction "2_2") (pintype "passive"))
    )
    (net (code "91") (name "unconnected-(OLED1-C1N-Pad4)") (class "Default")
      (node (ref "OLED1") (pin "4") (pinfunction "C1N_4") (pintype "passive"))
    )
    (net (code "92") (name "unconnected-(OLED1-C1P-Pad3)") (class "Default")
      (node (ref "OLED1") (pin "3") (pinfunction "C1P_3") (pintype "passive"))
    )
    (net (code "93") (name "unconnected-(OLED1-C2N-Pad2)") (class "Default")
      (node (ref "OLED1") (pin "2") (pinfunction "C2N_2") (pintype "passive"))
    )
    (net (code "94") (name "unconnected-(OLED1-C2P-Pad1)") (class "Default")
      (node (ref "OLED1") (pin "1") (pinfunction "C2P_1") (pintype "passive"))
    )
    (net (code "95") (name "unconnected-(OLED1-RES#-Pad9)") (class "Default")
      (node (ref "OLED1") (pin "9") (pinfunction "RES#_9") (pintype "passive"))
    )
    (net (code "96") (name "unconnected-(OLED1-VBREF-Pad6)") (class "Default")
      (node (ref "OLED1") (pin "6") (pinfunction "VBREF_6") (pintype "passive"))
    )
    (net (code "97") (name "unconnected-(U1-CTS#-Pad9)") (class "Default")
      (node (ref "U1") (pin "9") (pinfunction "CTS#_9") (pintype "passive"))
    )
    (net (code "98") (name "unconnected-(U1-DCD#-Pad12)") (class "Default")
      (node (ref "U1") (pin "12") (pinfunction "DCD#_12") (pintype "passive"))
    )
    (net (code "99") (name "unconnected-(U1-DSR#-Pad10)") (class "Default")
      (node (ref "U1") (pin "10") (pinfunction "DSR#_10") (pintype "passive"))
    )
    (net (code "100") (name "unconnected-(U1-R232-Pad15)") (class "Default")
      (node (ref "U1") (pin "15") (pinfunction "R232_15") (pintype "passive"))
    )
    (net (code "101") (name "unconnected-(U1-RI#-Pad11)") (class "Default")
      (node (ref "U1") (pin "11") (pinfunction "RI#_11") (pintype "passive"))
    )
    (net (code "102") (name "unconnected-(U3-Output-Pad4)") (class "Default")
      (node (ref "U3") (pin "4") (pinfunction "Output_4") (pintype "passive+no_connect"))
    )
    (net (code "103") (name "unconnected-(U5-AUX_CL-Pad7)") (class "Default")
      (node (ref "U5") (pin "7") (pinfunction "AUX_CL_7") (pintype "passive"))
    )
    (net (code "104") (name "unconnected-(U5-AUX_DA-Pad6)") (class "Default")
      (node (ref "U5") (pin "6") (pinfunction "AUX_DA_6") (pintype "passive"))
    )
    (net (code "105") (name "unconnected-(U5-NC-Pad2)") (class "Default")
      (node (ref "U5") (pin "2") (pinfunction "NC_2") (pintype "passive"))
    )
    (net (code "106") (name "unconnected-(U5-NC-Pad3)") (class "Default")
      (node (ref "U5") (pin "3") (pinfunction "NC_3") (pintype "passive"))
    )
    (net (code "107") (name "unconnected-(U5-NC-Pad4)") (class "Default")
      (node (ref "U5") (pin "4") (pinfunction "NC_4") (pintype "passive"))
    )
    (net (code "108") (name "unconnected-(U5-NC-Pad5)") (class "Default")
      (node (ref "U5") (pin "5") (pinfunction "NC_5") (pintype "passive"))
    )
    (net (code "109") (name "unconnected-(U5-NC-Pad14)") (class "Default")
      (node (ref "U5") (pin "14") (pinfunction "NC_14") (pintype "passive"))
    )
    (net (code "110") (name "unconnected-(U5-NC-Pad15)") (class "Default")
      (node (ref "U5") (pin "15") (pinfunction "NC_15") (pintype "passive"))
    )
    (net (code "111") (name "unconnected-(U5-NC-Pad16)") (class "Default")
      (node (ref "U5") (pin "16") (pinfunction "NC_16") (pintype "passive"))
    )
    (net (code "112") (name "unconnected-(U5-NC-Pad17)") (class "Default")
      (node (ref "U5") (pin "17") (pinfunction "NC_17") (pintype "passive"))
    )
    (net (code "113") (name "unconnected-(U5-RESV-Pad19)") (class "Default")
      (node (ref "U5") (pin "19") (pinfunction "RESV_19") (pintype "passive"))
    )
    (net (code "114") (name "unconnected-(U5-RESV-Pad21)") (class "Default")
      (node (ref "U5") (pin "21") (pinfunction "RESV_21") (pintype "passive"))
    )
    (net (code "115") (name "unconnected-(U5-RESV-Pad22)") (class "Default")
      (node (ref "U5") (pin "22") (pinfunction "RESV_22") (pintype "passive"))
    )
    (net (code "116") (name "unconnected-(U6-DRDY-Pad15)") (class "Default")
      (node (ref "U6") (pin "15") (pinfunction "DRDY_15") (pintype "passive"))
    )
    (net (code "117") (name "unconnected-(U6-I2C{slash}SPI-Pad6)") (class "Default")
      (node (ref "U6") (pin "6") (pinfunction "I2C/SPI_6") (pintype "passive"))
    )
    (net (code "118") (name "unconnected-(U6-NC-Pad3)") (class "Default")
      (node (ref "U6") (pin "3") (pinfunction "NC_3") (pintype "passive"))
    )
    (net (code "119") (name "unconnected-(U6-NC-Pad5)") (class "Default")
      (node (ref "U6") (pin "5") (pinfunction "NC_5") (pintype "passive"))
    )
    (net (code "120") (name "unconnected-(U6-NC-Pad7)") (class "Default")
      (node (ref "U6") (pin "7") (pinfunction "NC_7") (pintype "passive"))
    )
    (net (code "121") (name "unconnected-(U6-NC-Pad14)") (class "Default")
      (node (ref "U6") (pin "14") (pinfunction "NC_14") (pintype "passive"))
    )
    (net (code "122") (name "unconnected-(U6-S1-Pad4)") (class "Default")
      (node (ref "U6") (pin "4") (pinfunction "S1_4") (pintype "passive"))
    )
    (net (code "123") (name "unconnected-(U7-SDO-Pad6)") (class "Default")
      (node (ref "U7") (pin "6") (pinfunction "SDO_6") (pintype "passive"))
    )
    (net (code "124") (name "unconnected-(USB1-SBU1-PadA8)") (class "Default")
      (node (ref "USB1") (pin "A8") (pinfunction "SBU1_A8") (pintype "passive"))
    )
    (net (code "125") (name "unconnected-(USB1-SBU2-PadB8)") (class "Default")
      (node (ref "USB1") (pin "B8") (pinfunction "SBU2_B8") (pintype "passive"))
    )
    (net (code "126") (name "unconnected-(X1-GND-Pad2)") (class "Default")
      (node (ref "X1") (pin "2") (pinfunction "GND_2") (pintype "passive"))
    )
    (net (code "127") (name "unconnected-(X1-GND-Pad4)") (class "Default")
      (node (ref "X1") (pin "4") (pinfunction "GND_4") (pintype "passive"))
    )
    (net (code "128") (name "unconnected-(X2-GND-Pad2)") (class "Default")
      (node (ref "X2") (pin "2") (pinfunction "GND_2") (pintype "passive"))
    )
    (net (code "129") (name "unconnected-(X2-GND-Pad4)") (class "Default")
      (node (ref "X2") (pin "4") (pinfunction "GND_4") (pintype "passive"))
    )
  )
)
